# PAPRE.net
KiCad netlist of a schematic drawn in Altium Designer
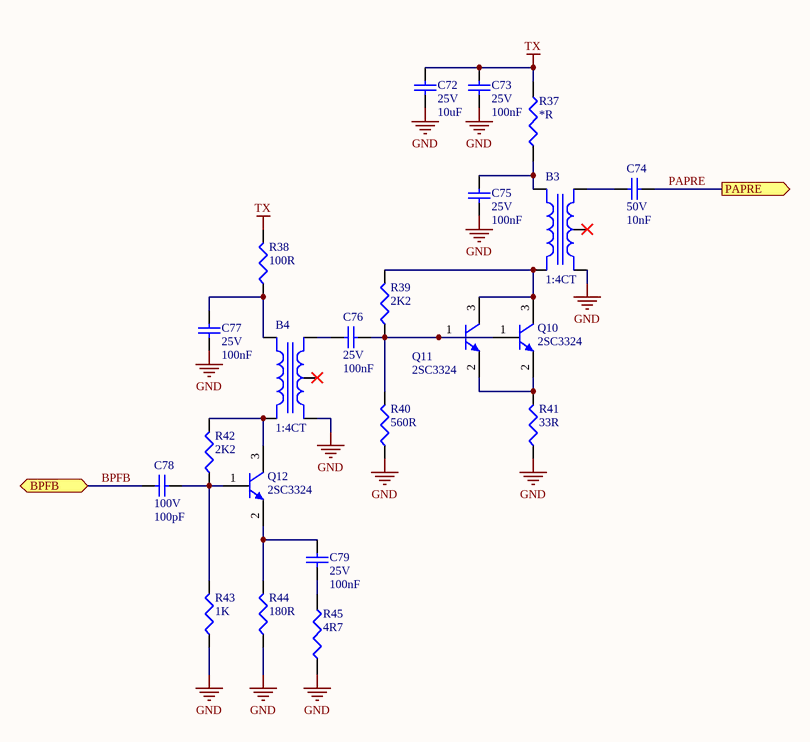
[diagram p0: PAPRE.SchDoc]

(export (version "E")
  (design (tool "Eeschema 10.0.6"))
  (components
    (comp (ref "B3")
      (value "1:4CT")
      (footprint "CX2047LANL")
      (description "Balun 4CT:1")
      (libsource (lib "NavarroIND") (part "BALUN CX2047LANL"))
    )
    (comp (ref "B4")
      (value "1:4CT")
      (footprint "CX2047LANL")
      (description "Balun 4CT:1")
      (libsource (lib "NavarroIND") (part "BALUN CX2047LANL"))
    )
    (comp (ref "C72")
      (value "10uF")
      (footprint "CC0805")
      (description "Capacitor (Semiconductor SIM Model)")
      (fields (field (name "TENSÃO") "25V") (field (name "Comment") "Capacitor Cerâmico"))
      (libsource (lib "NavarroCAP") (part "Cap 10uF 25V 0805 X5R"))
    )
    (comp (ref "C73")
      (value "100nF")
      (footprint "CC0603")
      (description "Capacitor (Semiconductor SIM Model)")
      (fields (field (name "TENSÃO") "25V") (field (name "Comment") "Capacitor Cerâmico"))
      (libsource (lib "NavarroCAP") (part "Cap 100nF 25V 0603 X7R"))
    )
    (comp (ref "C74")
      (value "10nF")
      (footprint "CC0603")
      (description "Capacitor (Semiconductor SIM Model)")
      (fields (field (name "TENSÃO") "50V") (field (name "Comment") "Capacitor Cerâmico"))
      (libsource (lib "NavarroCAP") (part "Cap 10nF 50V 0603 X7R 5%"))
    )
    (comp (ref "C75")
      (value "100nF")
      (footprint "CC0603")
      (description "Capacitor (Semiconductor SIM Model)")
      (fields (field (name "TENSÃO") "25V") (field (name "Comment") "Capacitor Cerâmico"))
      (libsource (lib "NavarroCAP") (part "Cap 100nF 25V 0603 X7R"))
    )
    (comp (ref "C76")
      (value "100nF")
      (footprint "CC0603")
      (description "Capacitor (Semiconductor SIM Model)")
      (fields (field (name "TENSÃO") "25V") (field (name "Comment") "Capacitor Cerâmico"))
      (libsource (lib "NavarroCAP") (part "Cap 100nF 25V 0603 X7R"))
    )
    (comp (ref "C77")
      (value "100nF")
      (footprint "CC0603")
      (description "Capacitor (Semiconductor SIM Model)")
      (fields (field (name "TENSÃO") "25V") (field (name "Comment") "Capacitor Cerâmico"))
      (libsource (lib "NavarroCAP") (part "Cap 100nF 25V 0603 X7R"))
    )
    (comp (ref "C78")
      (value "100pF")
      (footprint "CC0603")
      (description "Capacitor (Semiconductor SIM Model)")
      (fields (field (name "TENSÃO") "100V") (field (name "Comment") "Capacitor Cerâmico"))
      (libsource (lib "NavarroCAP") (part "Cap 100pF 100V 0603 NP0"))
    )
    (comp (ref "C79")
      (value "100nF")
      (footprint "CC0603")
      (description "Capacitor (Semiconductor SIM Model)")
      (fields (field (name "TENSÃO") "25V") (field (name "Comment") "Capacitor Cerâmico"))
      (libsource (lib "NavarroCAP") (part "Cap 100nF 25V 0603 X7R"))
    )
    (comp (ref "Q10")
      (value "2SC3324")
      (footprint "SOT-23-3N")
      (description "NPN General Purpose Amplifier")
      (libsource (lib "NavarroSEMI") (part "TRS 2SC3324 120V 100mA SOT-23-3"))
    )
    (comp (ref "Q11")
      (value "2SC3324")
      (footprint "SOT-23-3N")
      (description "NPN General Purpose Amplifier")
      (libsource (lib "NavarroSEMI") (part "TRS 2SC3324 120V 100mA SOT-23-3"))
    )
    (comp (ref "Q12")
      (value "2SC3324")
      (footprint "SOT-23-3N")
      (description "NPN General Purpose Amplifier")
      (libsource (lib "NavarroSEMI") (part "TRS 2SC3324 120V 100mA SOT-23-3"))
    )
    (comp (ref "R37")
      (value "*R")
      (footprint "CC0603")
      (description "Resistor")
      (libsource (lib "NavarroRES") (part "Res - $Val $% $Footprint $Pot"))
    )
    (comp (ref "R38")
      (value "100R")
      (footprint "CC0603")
      (description "Resistor")
      (libsource (lib "NavarroRES") (part "Res 100R 5% 0603 1/10W"))
    )
    (comp (ref "R39")
      (value "2K2")
      (footprint "CC0603")
      (description "Resistor")
      (libsource (lib "NavarroRES") (part "Res 2K2 5% 0603 1/10W"))
    )
    (comp (ref "R40")
      (value "560R")
      (footprint "CC0603")
      (description "Resistor")
      (libsource (lib "NavarroRES") (part "Res 560R 1% 0603 1/8W"))
    )
    (comp (ref "R41")
      (value "33R")
      (footprint "CC0603")
      (description "Resistor")
      (libsource (lib "NavarroRES") (part "Res 33R 1% 0603 1/10W"))
    )
    (comp (ref "R42")
      (value "2K2")
      (footprint "CC0603")
      (description "Resistor")
      (libsource (lib "NavarroRES") (part "Res 2K2 5% 0603 1/10W"))
    )
    (comp (ref "R43")
      (value "1K")
      (footprint "CC0603")
      (description "Resistor")
      (libsource (lib "NavarroRES") (part "Res 1K 1% 0603 1/10W"))
    )
    (comp (ref "R44")
      (value "180R")
      (footprint "CC0603")
      (description "Resistor")
      (libsource (lib "NavarroRES") (part "Res 180R 1% 0603 1/10W"))
    )
    (comp (ref "R45")
      (value "4R7")
      (footprint "CC0603")
      (description "Resistor")
      (libsource (lib "NavarroRES") (part "Res 4R7 1% 0603 1/10W"))
    )
  )
  (nets
    (net (code "1") (name "/BPFB") (class "Default")
      (node (ref "C78") (pin "1") (pinfunction "1_1") (pintype "passive"))
    )
    (net (code "2") (name "/PAPRE") (class "Default")
      (node (ref "C74") (pin "1") (pinfunction "1_1") (pintype "passive"))
    )
    (net (code "3") (name "GND") (class "Default")
      (node (ref "B3") (pin "3") (pinfunction "Pri-_3") (pintype "passive"))
      (node (ref "B4") (pin "3") (pinfunction "Pri-_3") (pintype "passive"))
      (node (ref "C72") (pin "1") (pinfunction "1_1") (pintype "passive"))
      (node (ref "C73") (pin "2") (pinfunction "2_2") (pintype "passive"))
      (node (ref "C75") (pin "2") (pinfunction "2_2") (pintype "passive"))
      (node (ref "C77") (pin "1") (pinfunction "1_1") (pintype "passive"))
      (node (ref "R40") (pin "1") (pinfunction "1_1") (pintype "passive"))
      (node (ref "R41") (pin "1") (pinfunction "1_1") (pintype "passive"))
      (node (ref "R43") (pin "1") (pinfunction "1_1") (pintype "passive"))
      (node (ref "R44") (pin "1") (pinfunction "1_1") (pintype "passive"))
      (node (ref "R45") (pin "1") (pinfunction "1_1") (pintype "passive"))
    )
    (net (code "4") (name "Net-(B3-Pri+)") (class "Default")
      (node (ref "B3") (pin "4") (pinfunction "Pri+_4") (pintype "passive"))
      (node (ref "Q10") (pin "3") (pinfunction "C_3") (pintype "passive"))
      (node (ref "Q11") (pin "3") (pinfunction "C_3") (pintype "passive"))
      (node (ref "R39") (pin "2") (pinfunction "2_2") (pintype "passive"))
    )
    (net (code "5") (name "Net-(B3-Sec+-Pad1)") (class "Default")
      (node (ref "B3") (pin "1") (pinfunction "Sec+_1") (pintype "passive"))
      (node (ref "C74") (pin "2") (pinfunction "2_2") (pintype "passive"))
    )
    (net (code "6") (name "Net-(B3-Sec-)") (class "Default")
      (node (ref "B3") (pin "6") (pinfunction "Sec-_6") (pintype "passive"))
      (node (ref "C75") (pin "1") (pinfunction "1_1") (pintype "passive"))
      (node (ref "R37") (pin "1") (pinfunction "1_1") (pintype "passive"))
    )
    (net (code "7") (name "Net-(B4-Pri+)") (class "Default")
      (node (ref "B4") (pin "4") (pinfunction "Pri+_4") (pintype "passive"))
      (node (ref "Q12") (pin "3") (pinfunction "C_3") (pintype "passive"))
      (node (ref "R42") (pin "2") (pinfunction "2_2") (pintype "passive"))
    )
    (net (code "8") (name "Net-(B4-Sec+-Pad1)") (class "Default")
      (node (ref "B4") (pin "1") (pinfunction "Sec+_1") (pintype "passive"))
      (node (ref "C76") (pin "2") (pinfunction "2_2") (pintype "passive"))
    )
    (net (code "9") (name "Net-(B4-Sec-)") (class "Default")
      (node (ref "B4") (pin "6") (pinfunction "Sec-_6") (pintype "passive"))
      (node (ref "C77") (pin "2") (pinfunction "2_2") (pintype "passive"))
      (node (ref "R38") (pin "1") (pinfunction "1_1") (pintype "passive"))
    )
    (net (code "10") (name "Net-(C79-Pad1)") (class "Default")
      (node (ref "C79") (pin "1") (pinfunction "1_1") (pintype "passive"))
      (node (ref "R45") (pin "2") (pinfunction "2_2") (pintype "passive"))
    )
    (net (code "11") (name "Net-(Q10-B)") (class "Default")
      (node (ref "C76") (pin "1") (pinfunction "1_1") (pintype "passive"))
      (node (ref "Q10") (pin "1") (pinfunction "B_1") (pintype "passive"))
      (node (ref "Q11") (pin "1") (pinfunction "B_1") (pintype "passive"))
      (node (ref "R39") (pin "1") (pinfunction "1_1") (pintype "passive"))
      (node (ref "R40") (pin "2") (pinfunction "2_2") (pintype "passive"))
    )
    (net (code "12") (name "Net-(Q10-E)") (class "Default")
      (node (ref "Q10") (pin "2") (pinfunction "E_2") (pintype "passive"))
      (node (ref "Q11") (pin "2") (pinfunction "E_2") (pintype "passive"))
      (node (ref "R41") (pin "2") (pinfunction "2_2") (pintype "passive"))
    )
    (net (code "13") (name "Net-(Q12-B)") (class "Default")
      (node (ref "C78") (pin "2") (pinfunction "2_2") (pintype "passive"))
      (node (ref "Q12") (pin "1") (pinfunction "B_1") (pintype "passive"))
      (node (ref "R42") (pin "1") (pinfunction "1_1") (pintype "passive"))
      (node (ref "R43") (pin "2") (pinfunction "2_2") (pintype "passive"))
    )
    (net (code "14") (name "Net-(Q12-E)") (class "Default")
      (node (ref "C79") (pin "2") (pinfunction "2_2") (pintype "passive"))
      (node (ref "Q12") (pin "2") (pinfunction "E_2") (pintype "passive"))
      (node (ref "R44") (pin "2") (pinfunction "2_2") (pintype "passive"))
    )
    (net (code "15") (name "TX") (class "Default")
      (node (ref "C72") (pin "2") (pinfunction "2_2") (pintype "passive"))
      (node (ref "C73") (pin "1") (pinfunction "1_1") (pintype "passive"))
      (node (ref "R37") (pin "2") (pinfunction "2_2") (pintype "passive"))
      (node (ref "R38") (pin "2") (pinfunction "2_2") (pintype "passive"))
    )
    (net (code "16") (name "unconnected-(B3-Sec+-Pad2)") (class "Default")
      (node (ref "B3") (pin "2") (pinfunction "Sec+_2") (pintype "passive+no_connect"))
    )
    (net (code "17") (name "unconnected-(B4-Sec+-Pad2)") (class "Default")
      (node (ref "B4") (pin "2") (pinfunction "Sec+_2") (pintype "passive+no_connect"))
    )
  )
)
